# carteBoutonsV1.net
KiCad netlist of a schematic drawn in EAGLE
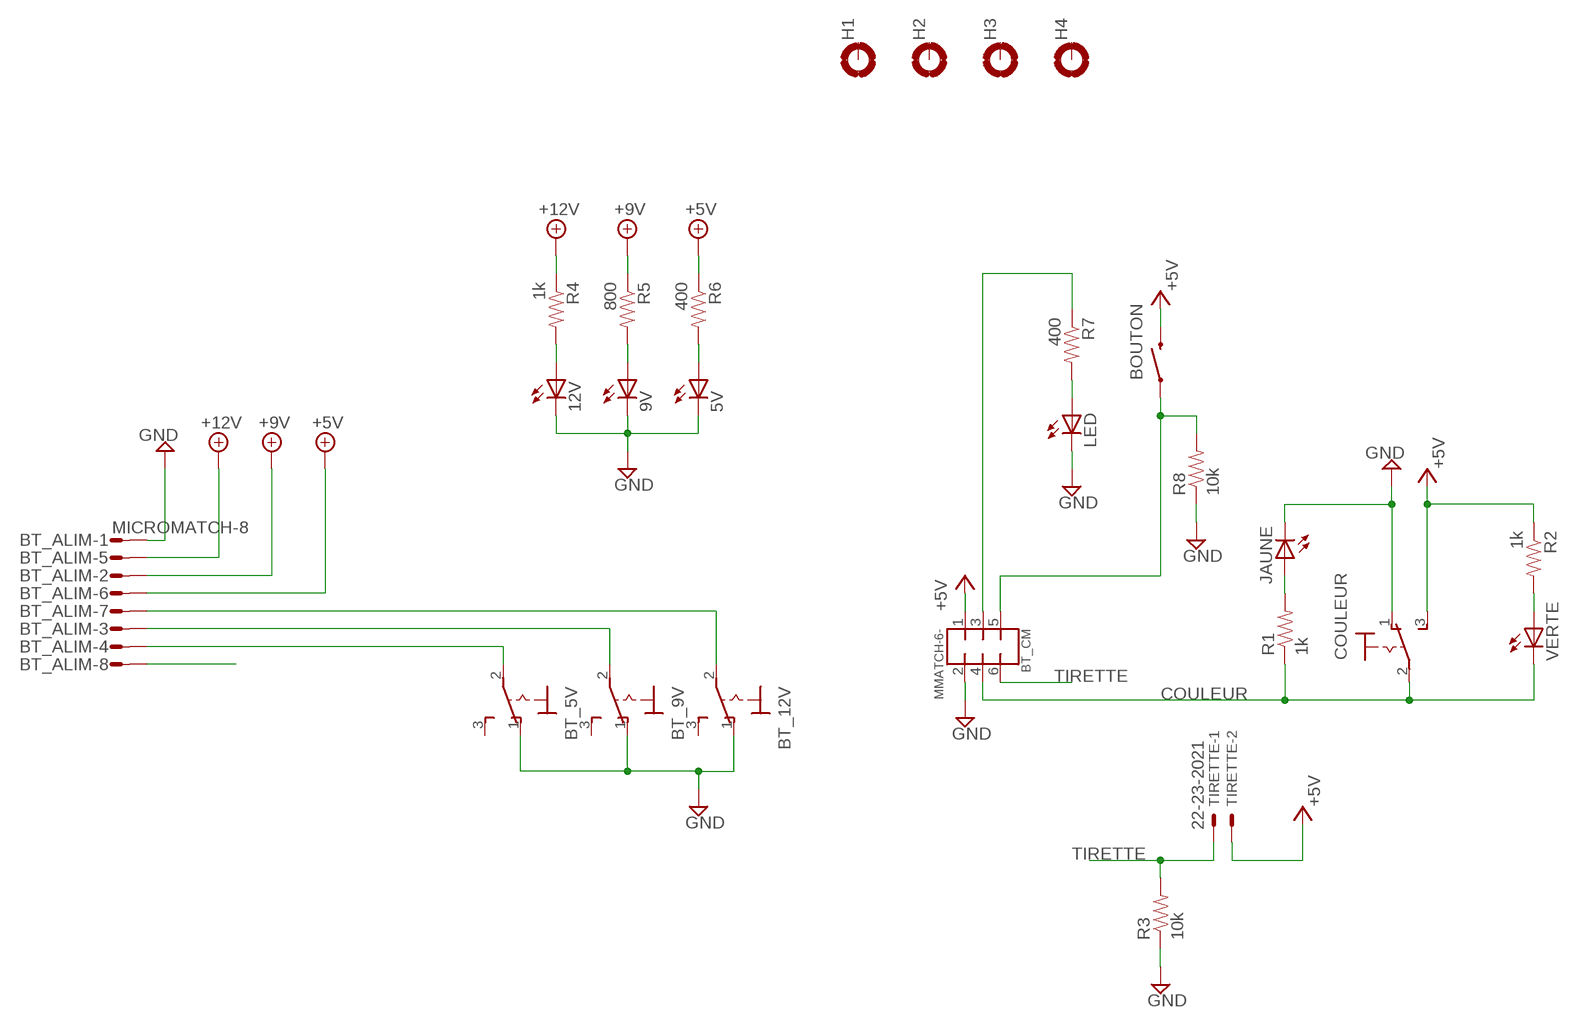
[diagram p0: schematic, sheet 1]

(export (version "E")
  (design (tool "Eeschema 10.0.6"))
  (components
    (comp (ref "5V")
      (value "LED3MM")
      (footprint "eagle-import:LED3MM")
      (libsource (lib "eagle-import") (part "LED3MM"))
    )
    (comp (ref "9V")
      (value "LED3MM")
      (footprint "eagle-import:LED3MM")
      (libsource (lib "eagle-import") (part "LED3MM"))
    )
    (comp (ref "12V")
      (value "LED3MM")
      (footprint "eagle-import:LED3MM")
      (libsource (lib "eagle-import") (part "LED3MM"))
    )
    (comp (ref "BOUTON")
      (value "SWITCH-MOMENTARY-2PTH")
      (footprint "eagle-import:TACTILE-PTH")
      (libsource (lib "eagle-import") (part "SWITCH-MOMENTARY-2PTH"))
    )
    (comp (ref "BT_5V")
      (value "320-916")
      (footprint "eagle-import:320-916")
      (libsource (lib "eagle-import") (part "320-916"))
    )
    (comp (ref "BT_9V")
      (value "320-916")
      (footprint "eagle-import:320-916")
      (libsource (lib "eagle-import") (part "320-916"))
    )
    (comp (ref "BT_12V")
      (value "320-916")
      (footprint "eagle-import:320-916")
      (libsource (lib "eagle-import") (part "320-916"))
    )
    (comp (ref "BT_ALIM")
      (value "MICROMATCH-8")
      (footprint "eagle-import:MICROMATCH-8")
      (fields (field (name "MF") "FARNELL") (field (name "MPN") "7-215464-8"))
      (libsource (lib "eagle-import") (part "MICROMATCH-8"))
    )
    (comp (ref "BT_CM")
      (value "MMATCH-6-")
      (footprint "eagle-import:AMP-215079-6")
      (libsource (lib "eagle-import") (part "MMATCH-6-"))
    )
    (comp (ref "COULEUR")
      (value "320-916")
      (footprint "eagle-import:320-916")
      (libsource (lib "eagle-import") (part "320-916"))
    )
    (comp (ref "H1")
      (value "MOUNT-PAD-ROUND3.2")
      (footprint "eagle-import:3,2-PAD")
      (libsource (lib "eagle-import") (part "MOUNT-PAD-ROUND3.2"))
    )
    (comp (ref "H2")
      (value "MOUNT-PAD-ROUND3.2")
      (footprint "eagle-import:3,2-PAD")
      (libsource (lib "eagle-import") (part "MOUNT-PAD-ROUND3.2"))
    )
    (comp (ref "H3")
      (value "MOUNT-PAD-ROUND3.2")
      (footprint "eagle-import:3,2-PAD")
      (libsource (lib "eagle-import") (part "MOUNT-PAD-ROUND3.2"))
    )
    (comp (ref "H4")
      (value "MOUNT-PAD-ROUND3.2")
      (footprint "eagle-import:3,2-PAD")
      (libsource (lib "eagle-import") (part "MOUNT-PAD-ROUND3.2"))
    )
    (comp (ref "JAUNE")
      (value "LED3MM")
      (footprint "eagle-import:LED3MM")
      (libsource (lib "eagle-import") (part "LED3MM"))
    )
    (comp (ref "LED")
      (value "LED3MM")
      (footprint "eagle-import:LED3MM")
      (libsource (lib "eagle-import") (part "LED3MM"))
    )
    (comp (ref "R1")
      (value "1k")
      (footprint "eagle-import:0805")
      (libsource (lib "eagle-import") (part "RESISTOR0805-RES"))
    )
    (comp (ref "R2")
      (value "1k")
      (footprint "eagle-import:0805")
      (libsource (lib "eagle-import") (part "RESISTOR0805-RES"))
    )
    (comp (ref "R3")
      (value "10k")
      (footprint "eagle-import:0805")
      (libsource (lib "eagle-import") (part "RESISTOR0805-RES"))
    )
    (comp (ref "R4")
      (value "1k")
      (footprint "eagle-import:0805")
      (libsource (lib "eagle-import") (part "RESISTOR0805-RES"))
    )
    (comp (ref "R5")
      (value "800")
      (footprint "eagle-import:0805")
      (libsource (lib "eagle-import") (part "RESISTOR0805-RES"))
    )
    (comp (ref "R6")
      (value "400")
      (footprint "eagle-import:0805")
      (libsource (lib "eagle-import") (part "RESISTOR0805-RES"))
    )
    (comp (ref "R7")
      (value "400")
      (footprint "eagle-import:0805")
      (libsource (lib "eagle-import") (part "RESISTOR0805-RES"))
    )
    (comp (ref "R8")
      (value "10k")
      (footprint "eagle-import:0805")
      (libsource (lib "eagle-import") (part "RESISTOR0805-RES"))
    )
    (comp (ref "TIRETTE")
      (value "22-23-2021")
      (footprint "eagle-import:22-23-2021")
      (fields (field (name "MF") "MOLEX"))
      (libsource (lib "eagle-import") (part "22-23-2021"))
    )
    (comp (ref "VERTE")
      (value "LED3MM")
      (footprint "eagle-import:LED3MM")
      (libsource (lib "eagle-import") (part "LED3MM"))
    )
  )
  (nets
    (net (code "1") (name "+5V") (class "Default")
      (node (ref "BOUTON") (pin "3") (pinfunction "2_3") (pintype "passive"))
      (node (ref "BT_ALIM") (pin "6") (pinfunction "S_6") (pintype "passive"))
      (node (ref "BT_CM") (pin "1") (pinfunction "3_1") (pintype "bidirectional"))
      (node (ref "COULEUR") (pin "3") (pinfunction "S_3") (pintype "passive"))
      (node (ref "R2") (pin "1") (pinfunction "1_1") (pintype "passive"))
      (node (ref "R6") (pin "1") (pinfunction "1_1") (pintype "passive"))
      (node (ref "TIRETTE") (pin "2") (pinfunction "S_2") (pintype "passive"))
    )
    (net (code "2") (name "+9V") (class "Default")
      (node (ref "BT_ALIM") (pin "2") (pinfunction "S_2") (pintype "passive"))
      (node (ref "R5") (pin "1") (pinfunction "1_1") (pintype "passive"))
    )
    (net (code "3") (name "+12V") (class "Default")
      (node (ref "BT_ALIM") (pin "5") (pinfunction "S_5") (pintype "passive"))
      (node (ref "R4") (pin "1") (pinfunction "1_1") (pintype "passive"))
    )
    (net (code "4") (name "/COULEUR") (class "Default")
      (node (ref "BT_CM") (pin "4") (pinfunction "6_4") (pintype "bidirectional"))
      (node (ref "COULEUR") (pin "2") (pinfunction "P_2") (pintype "passive"))
      (node (ref "R1") (pin "1") (pinfunction "1_1") (pintype "passive"))
      (node (ref "VERTE") (pin "K") (pinfunction "C_K") (pintype "passive"))
    )
    (net (code "5") (name "/TIRETTE") (class "Default")
      (node (ref "BT_CM") (pin "6") (pinfunction "8_6") (pintype "bidirectional"))
      (node (ref "R3") (pin "2") (pinfunction "2_2") (pintype "passive"))
      (node (ref "TIRETTE") (pin "1") (pinfunction "S_1") (pintype "passive"))
    )
    (net (code "6") (name "GND") (class "Default")
      (node (ref "12V") (pin "K") (pinfunction "C_K") (pintype "passive"))
      (node (ref "5V") (pin "K") (pinfunction "C_K") (pintype "passive"))
      (node (ref "9V") (pin "K") (pinfunction "C_K") (pintype "passive"))
      (node (ref "BT_12V") (pin "1") (pinfunction "O_1") (pintype "passive"))
      (node (ref "BT_5V") (pin "1") (pinfunction "O_1") (pintype "passive"))
      (node (ref "BT_9V") (pin "1") (pinfunction "O_1") (pintype "passive"))
      (node (ref "BT_ALIM") (pin "1") (pinfunction "S_1") (pintype "passive"))
      (node (ref "BT_CM") (pin "2") (pinfunction "4_2") (pintype "bidirectional"))
      (node (ref "COULEUR") (pin "1") (pinfunction "O_1") (pintype "passive"))
      (node (ref "JAUNE") (pin "K") (pinfunction "C_K") (pintype "passive"))
      (node (ref "LED") (pin "K") (pinfunction "C_K") (pintype "passive"))
      (node (ref "R3") (pin "1") (pinfunction "1_1") (pintype "passive"))
      (node (ref "R8") (pin "1") (pinfunction "1_1") (pintype "passive"))
    )
    (net (code "7") (name "Net-(5V-PadA)") (class "Default")
      (node (ref "5V") (pin "A") (pinfunction "A_A") (pintype "passive"))
      (node (ref "R6") (pin "2") (pinfunction "2_2") (pintype "passive"))
    )
    (net (code "8") (name "Net-(9V-PadA)") (class "Default")
      (node (ref "9V") (pin "A") (pinfunction "A_A") (pintype "passive"))
      (node (ref "R5") (pin "2") (pinfunction "2_2") (pintype "passive"))
    )
    (net (code "9") (name "Net-(12V-PadA)") (class "Default")
      (node (ref "12V") (pin "A") (pinfunction "A_A") (pintype "passive"))
      (node (ref "R4") (pin "2") (pinfunction "2_2") (pintype "passive"))
    )
    (net (code "10") (name "Net-(BT_5V-P)") (class "Default")
      (node (ref "BT_5V") (pin "2") (pinfunction "P_2") (pintype "passive"))
      (node (ref "BT_ALIM") (pin "4") (pinfunction "S_4") (pintype "passive"))
    )
    (net (code "11") (name "Net-(BT_9V-P)") (class "Default")
      (node (ref "BT_9V") (pin "2") (pinfunction "P_2") (pintype "passive"))
      (node (ref "BT_ALIM") (pin "3") (pinfunction "S_3") (pintype "passive"))
    )
    (net (code "12") (name "Net-(BT_12V-P)") (class "Default")
      (node (ref "BT_12V") (pin "2") (pinfunction "P_2") (pintype "passive"))
      (node (ref "BT_ALIM") (pin "7") (pinfunction "S_7") (pintype "passive"))
    )
    (net (code "13") (name "Net-(BT_CM-5)") (class "Default")
      (node (ref "BT_CM") (pin "3") (pinfunction "5_3") (pintype "bidirectional"))
      (node (ref "R7") (pin "1") (pinfunction "1_1") (pintype "passive"))
    )
    (net (code "14") (name "Net-(BT_CM-7)") (class "Default")
      (node (ref "BOUTON") (pin "1") (pinfunction "1_1") (pintype "passive"))
      (node (ref "BT_CM") (pin "5") (pinfunction "7_5") (pintype "bidirectional"))
      (node (ref "R8") (pin "2") (pinfunction "2_2") (pintype "passive"))
    )
    (net (code "15") (name "Net-(JAUNE-PadA)") (class "Default")
      (node (ref "JAUNE") (pin "A") (pinfunction "A_A") (pintype "passive"))
      (node (ref "R1") (pin "2") (pinfunction "2_2") (pintype "passive"))
    )
    (net (code "16") (name "Net-(LED-PadA)") (class "Default")
      (node (ref "LED") (pin "A") (pinfunction "A_A") (pintype "passive"))
      (node (ref "R7") (pin "2") (pinfunction "2_2") (pintype "passive"))
    )
    (net (code "17") (name "Net-(R2-Pad2)") (class "Default")
      (node (ref "R2") (pin "2") (pinfunction "2_2") (pintype "passive"))
      (node (ref "VERTE") (pin "A") (pinfunction "A_A") (pintype "passive"))
    )
    (net (code "18") (name "unconnected-(BT_5V-S-Pad3)") (class "Default")
      (node (ref "BT_5V") (pin "3") (pinfunction "S_3") (pintype "passive"))
    )
    (net (code "19") (name "unconnected-(BT_9V-S-Pad3)") (class "Default")
      (node (ref "BT_9V") (pin "3") (pinfunction "S_3") (pintype "passive"))
    )
    (net (code "20") (name "unconnected-(BT_12V-S-Pad3)") (class "Default")
      (node (ref "BT_12V") (pin "3") (pinfunction "S_3") (pintype "passive"))
    )
    (net (code "21") (name "unconnected-(BT_ALIMH-S-Pad8)") (class "Default")
      (node (ref "BT_ALIM") (pin "8") (pinfunction "S_8") (pintype "passive"))
    )
    (net (code "22") (name "unconnected-(H1-MOUNT-PadB3,2)") (class "Default")
      (node (ref "H1") (pin "B3,2") (pinfunction "MOUNT_B3,2") (pintype "passive"))
    )
    (net (code "23") (name "unconnected-(H2-MOUNT-PadB3,2)") (class "Default")
      (node (ref "H2") (pin "B3,2") (pinfunction "MOUNT_B3,2") (pintype "passive"))
    )
    (net (code "24") (name "unconnected-(H3-MOUNT-PadB3,2)") (class "Default")
      (node (ref "H3") (pin "B3,2") (pinfunction "MOUNT_B3,2") (pintype "passive"))
    )
    (net (code "25") (name "unconnected-(H4-MOUNT-PadB3,2)") (class "Default")
      (node (ref "H4") (pin "B3,2") (pinfunction "MOUNT_B3,2") (pintype "passive"))
    )
  )
)
